# AMU-S07-V00-Alarm.net
KiCad netlist of a schematic drawn in Altium Designer
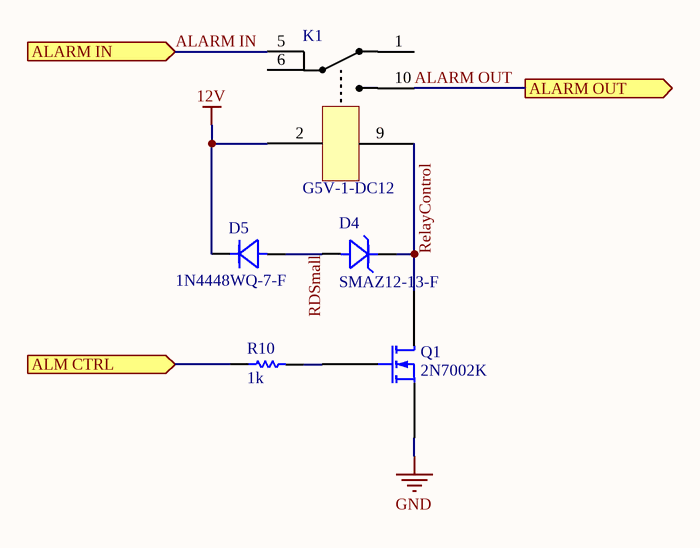
[diagram p0: AMU-S07-V00-Alarm.SchDoc]

(export (version "E")
  (design (tool "Eeschema 10.0.6"))
  (components
    (comp (ref "D4")
      (value "SMAZ12-13-F")
      (footprint "SMA")
      (description "Zener Diode 12V 1W ±5% Surface Mount SMA")
      (fields (field (name "MANUFACTURER") "ON Semiconductor") (field (name "MPN") "MM3Z56VB"))
      (libsource (lib "QUTMS_DiodeLibrary") (part "SMAZ12-13-F"))
    )
    (comp (ref "D5")
      (value "1N4448WQ-7-F")
      (footprint "SMA")
      (description "Diode, SMD, 75V, 5%, 250mA, SOD123")
      (fields
        (field (name "MANUFACTURER") "ON Semiconductor / Fairchild")
        (field (name "MANUFACTURER PART NUMBER") "1N914BWS")
      )
      (libsource (lib "QUTMS_DiodeLibrary") (part "1N4448WQ-7-F"))
    )
    (comp (ref "K1")
      (value "G5V-1-DC12")
      (footprint "G5V-1")
      (description "General Purpose Relay SPDT (1 Form C) Through Hole, 12V, 2A")
      (libsource (lib "QUTMS_RelayLibrary") (part "G5V-1-DC12"))
    )
    (comp (ref "Q1")
      (value "2N7002K")
      (footprint "SOT-23-3")
      (description "N-Channel 60V 300mA (Ta) 350mW (Ta) Surface Mount SOT-23 (TO-236AB)")
      (libsource (lib "QUTMS_Transistors") (part "2N7002K"))
    )
    (comp (ref "R10")
      (value "1k")
      (footprint "Res_ThinFilm_0603")
      (description "Resistor, SMD, 1k, 0.1W, 5%, 0603")
      (libsource (lib "StandardResistors") (part "1k 5% 0603"))
    )
  )
  (nets
    (net (code "1") (name "/ALARM IN") (class "Default")
      (node (ref "K1") (pin "5") (pinfunction "5_5") (pintype "passive"))
    )
    (net (code "2") (name "/ALARM OUT") (class "Default")
      (node (ref "K1") (pin "10") (pinfunction "10_10") (pintype "passive"))
    )
    (net (code "3") (name "/ALM CTRL") (class "Default")
      (node (ref "R10") (pin "1") (pinfunction "1_1") (pintype "passive"))
    )
    (net (code "4") (name "/RDSmall") (class "Default")
      (node (ref "D4") (pin "A") (pinfunction "Anode_A") (pintype "passive"))
      (node (ref "D5") (pin "A") (pinfunction "Anode_A") (pintype "passive"))
    )
    (net (code "5") (name "/RelayControl") (class "Default")
      (node (ref "D4") (pin "K") (pinfunction "Cathode_K") (pintype "passive"))
      (node (ref "K1") (pin "9") (pinfunction "9_9") (pintype "passive"))
      (node (ref "Q1") (pin "D") (pinfunction "D_D") (pintype "passive"))
    )
    (net (code "6") (name "12V") (class "Default")
      (node (ref "D5") (pin "K") (pinfunction "Cathode_K") (pintype "passive"))
      (node (ref "K1") (pin "2") (pinfunction "2_2") (pintype "passive"))
    )
    (net (code "7") (name "GND") (class "Default")
      (node (ref "Q1") (pin "S") (pinfunction "S_S") (pintype "passive"))
    )
    (net (code "8") (name "Net-(Q1-PadG)") (class "Default")
      (node (ref "Q1") (pin "G") (pinfunction "G_G") (pintype "passive"))
      (node (ref "R10") (pin "2") (pinfunction "2_2") (pintype "passive"))
    )
    (net (code "9") (name "unconnected-(K1-Pad1)") (class "Default")
      (node (ref "K1") (pin "1") (pinfunction "1_1") (pintype "passive"))
    )
    (net (code "10") (name "unconnected-(K1-Pad6)") (class "Default")
      (node (ref "K1") (pin "6") (pinfunction "6_6") (pintype "passive"))
    )
  )
)
